# radio.net
KiCad netlist of a schematic drawn in EAGLE
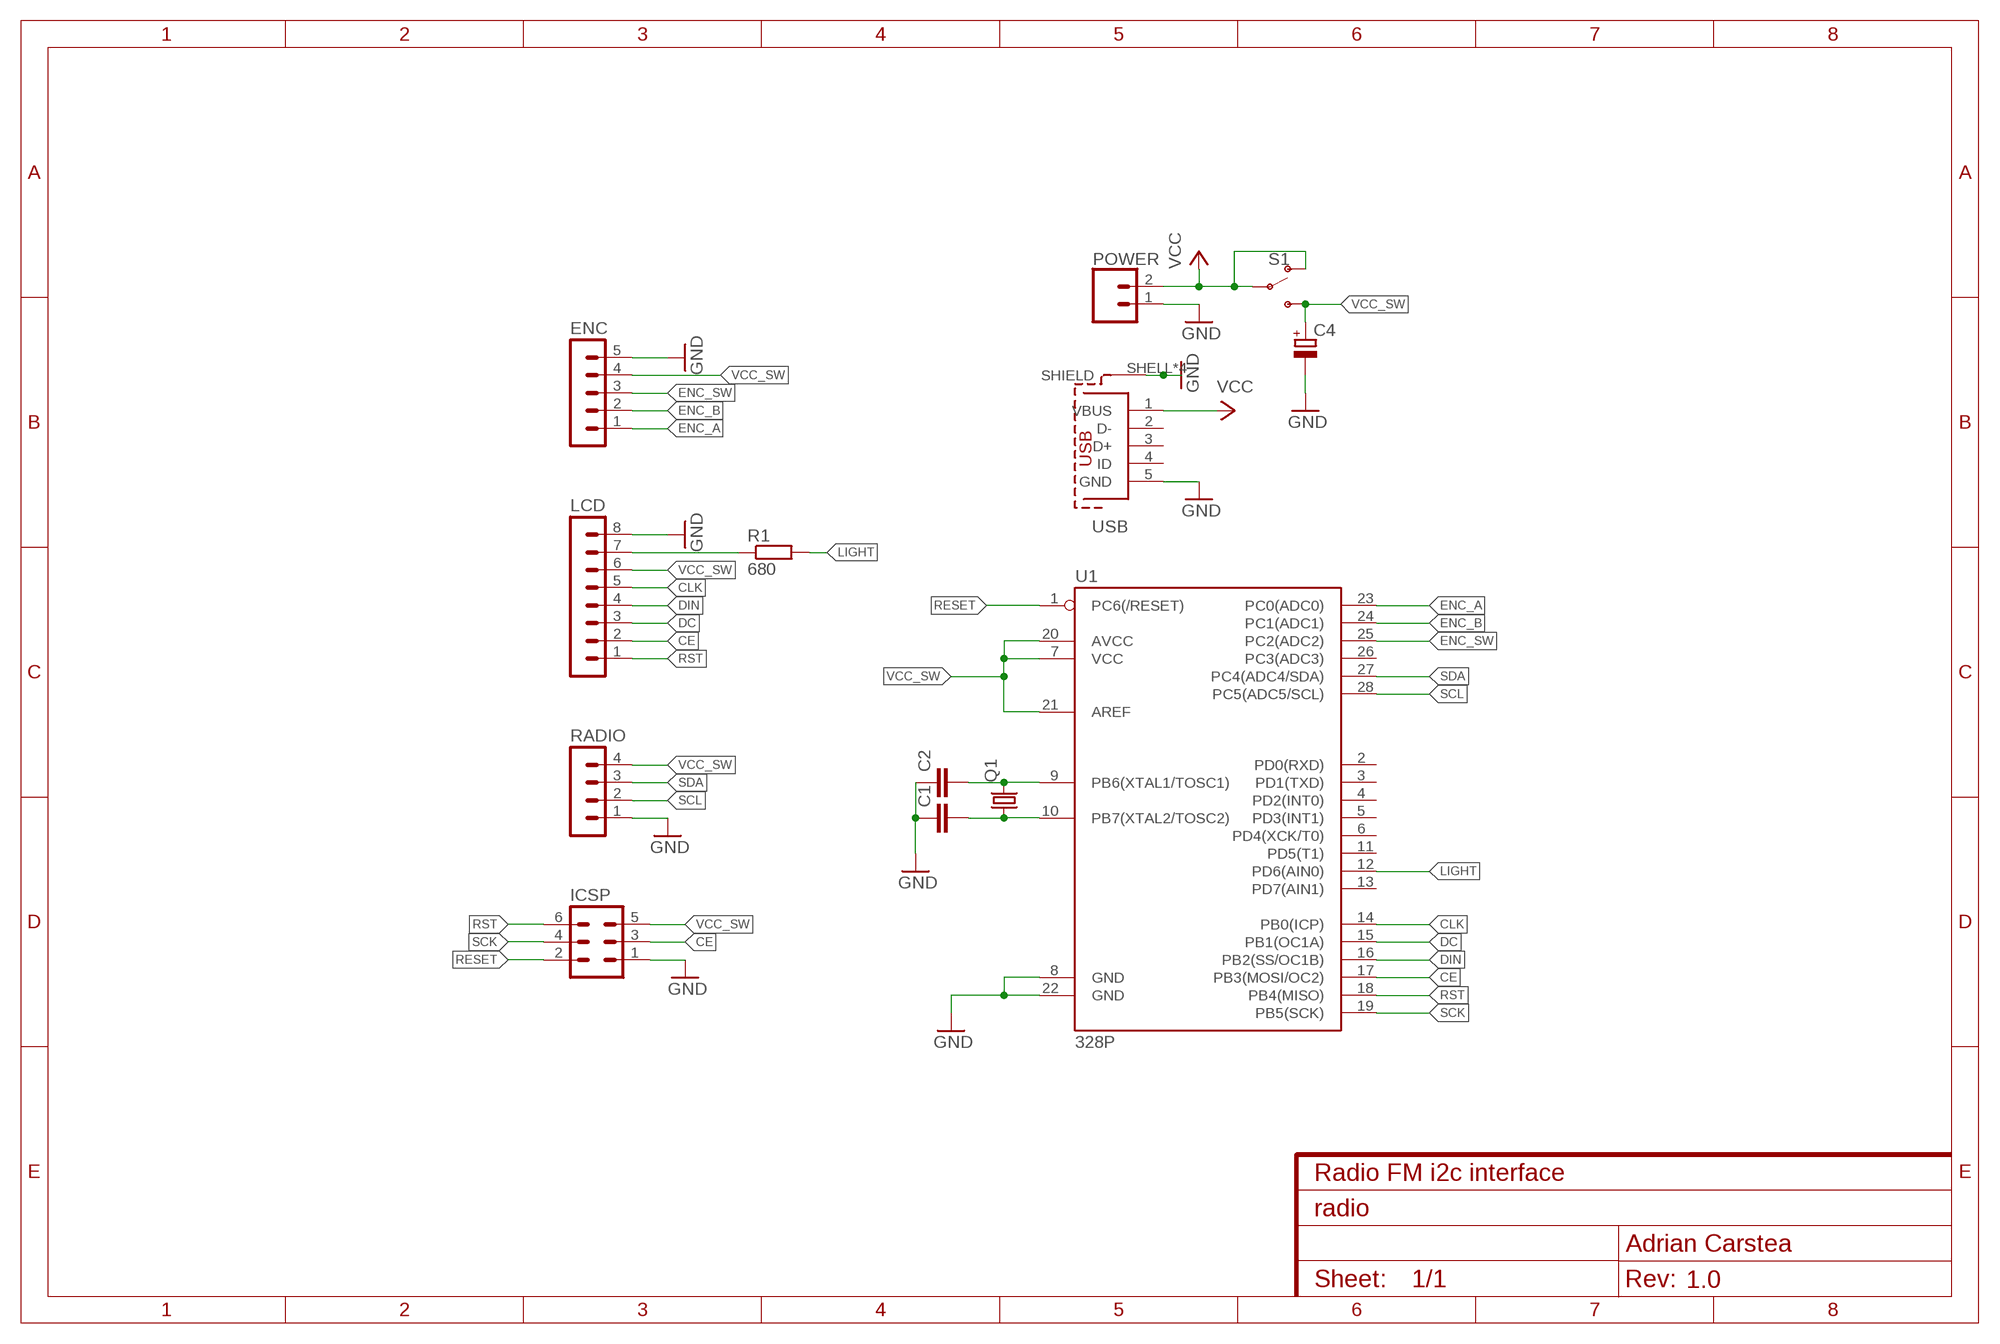
[diagram p0: schematic, sheet 1]

(export (version "E")
  (design (tool "Eeschema 10.0.6"))
  (components
    (comp (ref "C1")
      (value "C-EUC1206")
      (footprint "eagle-import:C1206")
      (libsource (lib "eagle-import") (part "C-EUC1206"))
    )
    (comp (ref "C2")
      (value "C-EUC1206")
      (footprint "eagle-import:C1206")
      (libsource (lib "eagle-import") (part "C-EUC1206"))
    )
    (comp (ref "C4")
      (value "CPOL-EUE5-10.5")
      (footprint "eagle-import:E5-10,5")
      (libsource (lib "eagle-import") (part "CPOL-EUE5-10.5"))
    )
    (comp (ref "ENC")
      (value "MA05-1")
      (footprint "eagle-import:MA05-1")
      (libsource (lib "eagle-import") (part "MA05-1"))
    )
    (comp (ref "ICSP")
      (value "MA03-2")
      (footprint "eagle-import:MA03-2")
      (libsource (lib "eagle-import") (part "MA03-2"))
    )
    (comp (ref "LCD")
      (value "MA08-1")
      (footprint "eagle-import:MA08-1")
      (libsource (lib "eagle-import") (part "MA08-1"))
    )
    (comp (ref "POWER")
      (value "CONN_02PTH3")
      (footprint "eagle-import:1X02_LONGPADS")
      (libsource (lib "eagle-import") (part "CONN_02PTH3"))
    )
    (comp (ref "Q1")
      (value "CRYSTALSM49")
      (footprint "eagle-import:SM49")
      (libsource (lib "eagle-import") (part "CRYSTALSM49"))
    )
    (comp (ref "R1")
      (value "680")
      (footprint "eagle-import:R0805")
      (libsource (lib "eagle-import") (part "R-EU_R0805"))
    )
    (comp (ref "RADIO")
      (value "MA04-1")
      (footprint "eagle-import:MA04-1")
      (libsource (lib "eagle-import") (part "MA04-1"))
    )
    (comp (ref "S1")
      (value "SWITCH-SPDT-PTH-11.6X4.0MM")
      (footprint "eagle-import:SWITCH_SPDT_PTH_11.6X4.0MM")
      (libsource (lib "eagle-import") (part "SWITCH-SPDT-PTH-11.6X4.0MM"))
    )
    (comp (ref "U1")
      (value "328P")
      (footprint "eagle-import:DIP28")
      (libsource (lib "eagle-import") (part "ATMEGA328P_PDIP"))
    )
    (comp (ref "USB")
      (value "629105136821")
      (footprint "eagle-import:629105136821")
      (libsource (lib "eagle-import") (part "629105136821"))
    )
  )
  (nets
    (net (code "1") (name "CE") (class "Default")
      (node (ref "ICSP") (pin "3") (pinfunction "3_3") (pintype "passive"))
      (node (ref "LCD") (pin "2") (pinfunction "2_2") (pintype "passive"))
      (node (ref "U1") (pin "17") (pinfunction "PB3(MOSI/OC2)_17") (pintype "bidirectional"))
    )
    (net (code "2") (name "CLK") (class "Default")
      (node (ref "LCD") (pin "5") (pinfunction "5_5") (pintype "passive"))
      (node (ref "U1") (pin "14") (pinfunction "PB0(ICP)_14") (pintype "bidirectional"))
    )
    (net (code "3") (name "DC") (class "Default")
      (node (ref "LCD") (pin "3") (pinfunction "3_3") (pintype "passive"))
      (node (ref "U1") (pin "15") (pinfunction "PB1(OC1A)_15") (pintype "bidirectional"))
    )
    (net (code "4") (name "DIN") (class "Default")
      (node (ref "LCD") (pin "4") (pinfunction "4_4") (pintype "passive"))
      (node (ref "U1") (pin "16") (pinfunction "PB2(SS/OC1B)_16") (pintype "bidirectional"))
    )
    (net (code "5") (name "ENC_A") (class "Default")
      (node (ref "ENC") (pin "1") (pinfunction "1_1") (pintype "passive"))
      (node (ref "U1") (pin "23") (pinfunction "PC0(ADC0)_23") (pintype "bidirectional"))
    )
    (net (code "6") (name "ENC_B") (class "Default")
      (node (ref "ENC") (pin "2") (pinfunction "2_2") (pintype "passive"))
      (node (ref "U1") (pin "24") (pinfunction "PC1(ADC1)_24") (pintype "bidirectional"))
    )
    (net (code "7") (name "ENC_SW") (class "Default")
      (node (ref "ENC") (pin "3") (pinfunction "3_3") (pintype "passive"))
      (node (ref "U1") (pin "25") (pinfunction "PC2(ADC2)_25") (pintype "bidirectional"))
    )
    (net (code "8") (name "GND") (class "Default")
      (node (ref "C1") (pin "1") (pinfunction "1_1") (pintype "passive"))
      (node (ref "C2") (pin "1") (pinfunction "1_1") (pintype "passive"))
      (node (ref "C4") (pin "-") (pinfunction "-_-") (pintype "passive"))
      (node (ref "ENC") (pin "5") (pinfunction "5_5") (pintype "passive"))
      (node (ref "ICSP") (pin "1") (pinfunction "1_1") (pintype "passive"))
      (node (ref "LCD") (pin "8") (pinfunction "8_8") (pintype "passive"))
      (node (ref "POWER") (pin "1") (pinfunction "1_1") (pintype "passive"))
      (node (ref "RADIO") (pin "1") (pinfunction "1_1") (pintype "passive"))
      (node (ref "U1") (pin "22") (pinfunction "GND_22") (pintype "bidirectional"))
      (node (ref "U1") (pin "8") (pinfunction "GND_8") (pintype "bidirectional"))
      (node (ref "USB") (pin "5") (pinfunction "GND_5") (pintype "passive"))
      (node (ref "USB") (pin "SHELL") (pinfunction "SHIELD_SHELL") (pintype "passive"))
      (node (ref "USB") (pin "SHELL1") (pinfunction "SHIELD_SHELL1") (pintype "passive"))
      (node (ref "USB") (pin "SHELL2") (pinfunction "SHIELD_SHELL2") (pintype "passive"))
      (node (ref "USB") (pin "SHELL3") (pinfunction "SHIELD_SHELL3") (pintype "passive"))
    )
    (net (code "9") (name "LIGHT") (class "Default")
      (node (ref "R1") (pin "2") (pinfunction "2_2") (pintype "passive"))
      (node (ref "U1") (pin "12") (pinfunction "PD6(AIN0)_12") (pintype "bidirectional"))
    )
    (net (code "10") (name "Net-(LCD-Pad7)") (class "Default")
      (node (ref "LCD") (pin "7") (pinfunction "7_7") (pintype "passive"))
      (node (ref "R1") (pin "1") (pinfunction "1_1") (pintype "passive"))
    )
    (net (code "11") (name "Net-(U1-PB6(XTAL1{slash}TOSC1))") (class "Default")
      (node (ref "C2") (pin "2") (pinfunction "2_2") (pintype "passive"))
      (node (ref "Q1") (pin "2") (pinfunction "2_2") (pintype "passive"))
      (node (ref "U1") (pin "9") (pinfunction "PB6(XTAL1/TOSC1)_9") (pintype "bidirectional"))
    )
    (net (code "12") (name "Net-(U1-PB7(XTAL2{slash}TOSC2))") (class "Default")
      (node (ref "C1") (pin "2") (pinfunction "2_2") (pintype "passive"))
      (node (ref "Q1") (pin "1") (pinfunction "1_1") (pintype "passive"))
      (node (ref "U1") (pin "10") (pinfunction "PB7(XTAL2/TOSC2)_10") (pintype "bidirectional"))
    )
    (net (code "13") (name "RESET") (class "Default")
      (node (ref "ICSP") (pin "2") (pinfunction "2_2") (pintype "passive"))
      (node (ref "U1") (pin "1") (pinfunction "PC6(/RESET)_1") (pintype "bidirectional"))
    )
    (net (code "14") (name "RST") (class "Default")
      (node (ref "ICSP") (pin "6") (pinfunction "6_6") (pintype "passive"))
      (node (ref "LCD") (pin "1") (pinfunction "1_1") (pintype "passive"))
      (node (ref "U1") (pin "18") (pinfunction "PB4(MISO)_18") (pintype "bidirectional"))
    )
    (net (code "15") (name "SCK") (class "Default")
      (node (ref "ICSP") (pin "4") (pinfunction "4_4") (pintype "passive"))
      (node (ref "U1") (pin "19") (pinfunction "PB5(SCK)_19") (pintype "bidirectional"))
    )
    (net (code "16") (name "SCL") (class "Default")
      (node (ref "RADIO") (pin "2") (pinfunction "2_2") (pintype "passive"))
      (node (ref "U1") (pin "28") (pinfunction "PC5(ADC5/SCL)_28") (pintype "bidirectional"))
    )
    (net (code "17") (name "SDA") (class "Default")
      (node (ref "RADIO") (pin "3") (pinfunction "3_3") (pintype "passive"))
      (node (ref "U1") (pin "27") (pinfunction "PC4(ADC4/SDA)_27") (pintype "bidirectional"))
    )
    (net (code "18") (name "VCC") (class "Default")
      (node (ref "POWER") (pin "2") (pinfunction "2_2") (pintype "passive"))
      (node (ref "S1") (pin "1") (pinfunction "O_1") (pintype "passive"))
      (node (ref "S1") (pin "2") (pinfunction "P_2") (pintype "passive"))
      (node (ref "USB") (pin "1") (pinfunction "VBUS_1") (pintype "passive"))
    )
    (net (code "19") (name "VCC_SW") (class "Default")
      (node (ref "C4") (pin "+") (pinfunction "+_+") (pintype "passive"))
      (node (ref "ENC") (pin "4") (pinfunction "4_4") (pintype "passive"))
      (node (ref "ICSP") (pin "5") (pinfunction "5_5") (pintype "passive"))
      (node (ref "LCD") (pin "6") (pinfunction "6_6") (pintype "passive"))
      (node (ref "RADIO") (pin "4") (pinfunction "4_4") (pintype "passive"))
      (node (ref "S1") (pin "3") (pinfunction "S_3") (pintype "passive"))
      (node (ref "U1") (pin "20") (pinfunction "AVCC_20") (pintype "bidirectional"))
      (node (ref "U1") (pin "21") (pinfunction "AREF_21") (pintype "bidirectional"))
      (node (ref "U1") (pin "7") (pinfunction "VCC_7") (pintype "bidirectional"))
    )
    (net (code "20") (name "unconnected-(U1-PC3(ADC3)-Pad26)") (class "Default")
      (node (ref "U1") (pin "26") (pinfunction "PC3(ADC3)_26") (pintype "bidirectional"))
    )
    (net (code "21") (name "unconnected-(U1-PD0(RXD)-Pad2)") (class "Default")
      (node (ref "U1") (pin "2") (pinfunction "PD0(RXD)_2") (pintype "bidirectional"))
    )
    (net (code "22") (name "unconnected-(U1-PD1(TXD)-Pad3)") (class "Default")
      (node (ref "U1") (pin "3") (pinfunction "PD1(TXD)_3") (pintype "bidirectional"))
    )
    (net (code "23") (name "unconnected-(U1-PD2(INT0)-Pad4)") (class "Default")
      (node (ref "U1") (pin "4") (pinfunction "PD2(INT0)_4") (pintype "bidirectional"))
    )
    (net (code "24") (name "unconnected-(U1-PD3(INT1)-Pad5)") (class "Default")
      (node (ref "U1") (pin "5") (pinfunction "PD3(INT1)_5") (pintype "bidirectional"))
    )
    (net (code "25") (name "unconnected-(U1-PD4(XCK{slash}T0)-Pad6)") (class "Default")
      (node (ref "U1") (pin "6") (pinfunction "PD4(XCK/T0)_6") (pintype "bidirectional"))
    )
    (net (code "26") (name "unconnected-(U1-PD5(T1)-Pad11)") (class "Default")
      (node (ref "U1") (pin "11") (pinfunction "PD5(T1)_11") (pintype "bidirectional"))
    )
    (net (code "27") (name "unconnected-(U1-PD7(AIN1)-Pad13)") (class "Default")
      (node (ref "U1") (pin "13") (pinfunction "PD7(AIN1)_13") (pintype "bidirectional"))
    )
    (net (code "28") (name "unconnected-(USB-D+-Pad3)") (class "Default")
      (node (ref "USB") (pin "3") (pinfunction "D+_3") (pintype "passive"))
    )
    (net (code "29") (name "unconnected-(USB-D--Pad2)") (class "Default")
      (node (ref "USB") (pin "2") (pinfunction "D-_2") (pintype "passive"))
    )
    (net (code "30") (name "unconnected-(USB-ID-Pad4)") (class "Default")
      (node (ref "USB") (pin "4") (pinfunction "ID_4") (pintype "passive"))
    )
  )
)
